# DevControl.net
KiCad netlist of a schematic drawn in EAGLE
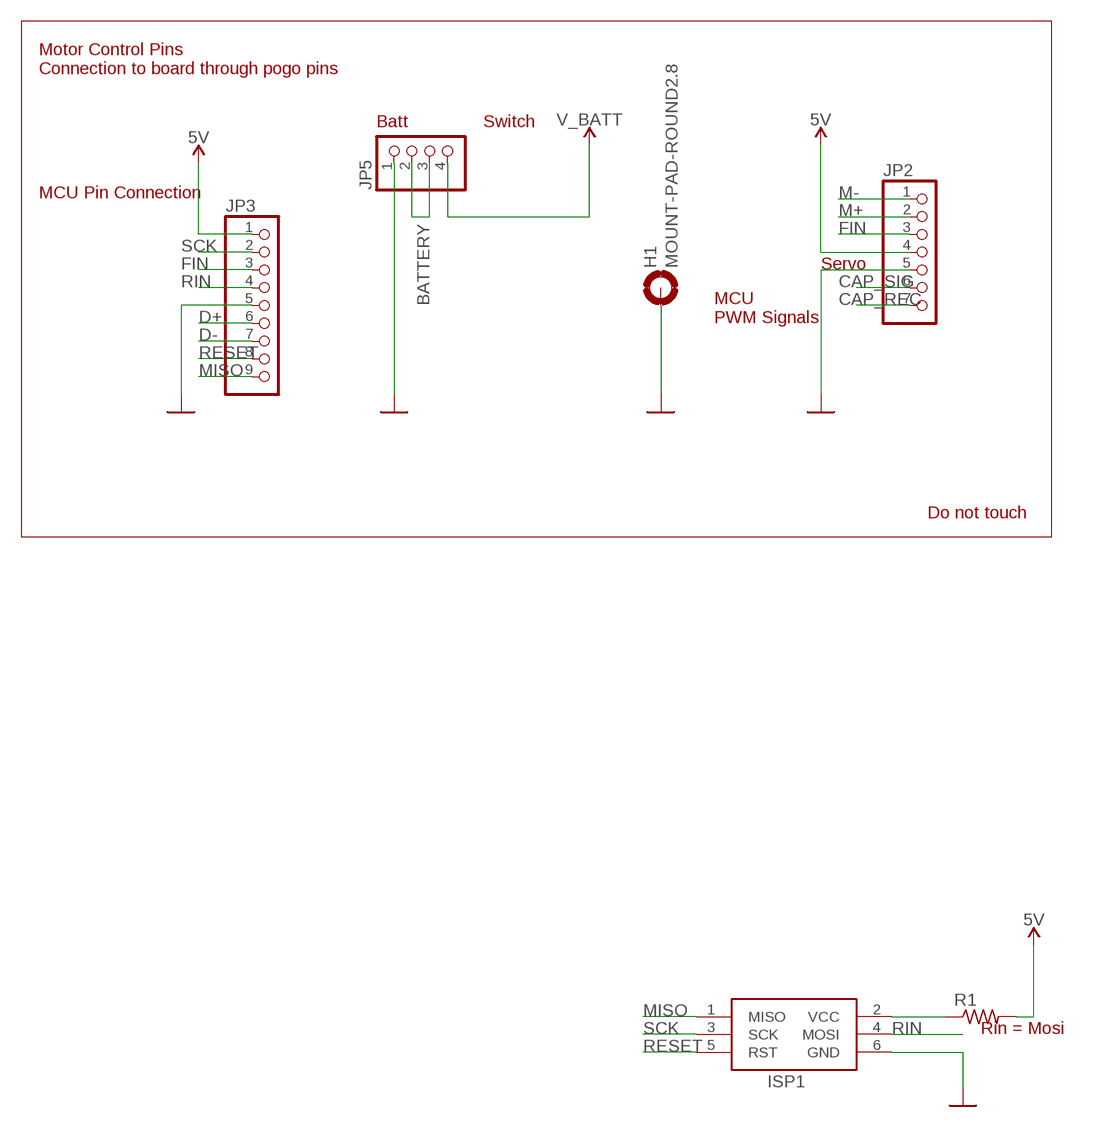
[diagram p0: schematic, sheet 1]

(export (version "E")
  (design (tool "Eeschema 10.0.6"))
  (components
    (comp (ref "H1")
      (value "MOUNT-PAD-ROUND2.8")
      (footprint "eagle-import:2,8-PAD")
      (libsource (lib "eagle-import") (part "MOUNT-PAD-ROUND2.8"))
    )
    (comp (ref "ISP1")
      (value "AVRISP-6")
      (footprint "eagle-import:AVRISP")
      (libsource (lib "eagle-import") (part "AVRISP-6"))
    )
    (comp (ref "JP2")
      (value "HEADER-1X7")
      (footprint "eagle-import:1X07_OVAL")
      (libsource (lib "eagle-import") (part "HEADER-1X7"))
    )
    (comp (ref "JP3")
      (value "HEADER-1X9")
      (footprint "eagle-import:1X09_OVAL")
      (libsource (lib "eagle-import") (part "HEADER-1X9"))
    )
    (comp (ref "JP5")
      (value "HEADER-1X4")
      (footprint "eagle-import:1X04_OVAL")
      (libsource (lib "eagle-import") (part "HEADER-1X4"))
    )
    (comp (ref "R1")
      (value "R-US_R0805")
      (footprint "eagle-import:R0805")
      (libsource (lib "eagle-import") (part "R-US_R0805"))
    )
  )
  (nets
    (net (code "1") (name "/BATTERY") (class "Default")
      (node (ref "JP5") (pin "2") (pinfunction "2_2") (pintype "passive"))
      (node (ref "JP5") (pin "3") (pinfunction "3_3") (pintype "passive"))
    )
    (net (code "2") (name "/CAP_REC") (class "Default")
      (node (ref "JP2") (pin "7") (pinfunction "7_7") (pintype "passive"))
    )
    (net (code "3") (name "/CAP_SIG") (class "Default")
      (node (ref "JP2") (pin "6") (pinfunction "6_6") (pintype "passive"))
    )
    (net (code "4") (name "/D+") (class "Default")
      (node (ref "JP3") (pin "6") (pinfunction "6_6") (pintype "passive"))
    )
    (net (code "5") (name "/D-") (class "Default")
      (node (ref "JP3") (pin "7") (pinfunction "7_7") (pintype "passive"))
    )
    (net (code "6") (name "/FIN") (class "Default")
      (node (ref "JP2") (pin "3") (pinfunction "3_3") (pintype "passive"))
      (node (ref "JP3") (pin "3") (pinfunction "3_3") (pintype "passive"))
    )
    (net (code "7") (name "/M+") (class "Default")
      (node (ref "JP2") (pin "2") (pinfunction "2_2") (pintype "passive"))
    )
    (net (code "8") (name "/M-") (class "Default")
      (node (ref "JP2") (pin "1") (pinfunction "1_1") (pintype "passive"))
    )
    (net (code "9") (name "/MISO") (class "Default")
      (node (ref "ISP1") (pin "1") (pinfunction "MISO_1") (pintype "input"))
      (node (ref "JP3") (pin "9") (pinfunction "9_9") (pintype "passive"))
    )
    (net (code "10") (name "/RESET") (class "Default")
      (node (ref "ISP1") (pin "5") (pinfunction "RST_5") (pintype "output"))
      (node (ref "JP3") (pin "8") (pinfunction "8_8") (pintype "passive"))
    )
    (net (code "11") (name "/RIN") (class "Default")
      (node (ref "ISP1") (pin "4") (pinfunction "MOSI_4") (pintype "output"))
      (node (ref "JP3") (pin "4") (pinfunction "4_4") (pintype "passive"))
    )
    (net (code "12") (name "/SCK") (class "Default")
      (node (ref "ISP1") (pin "3") (pinfunction "SCK_3") (pintype "output"))
      (node (ref "JP3") (pin "2") (pinfunction "2_2") (pintype "passive"))
    )
    (net (code "13") (name "5V") (class "Default")
      (node (ref "JP2") (pin "4") (pinfunction "4_4") (pintype "passive"))
      (node (ref "JP3") (pin "1") (pinfunction "1_1") (pintype "passive"))
      (node (ref "R1") (pin "2") (pinfunction "2_2") (pintype "passive"))
    )
    (net (code "14") (name "GND") (class "Default")
      (node (ref "H1") (pin "B2,8") (pinfunction "MOUNT_B2,8") (pintype "passive"))
      (node (ref "ISP1") (pin "6") (pinfunction "GND_6") (pintype "power_in"))
      (node (ref "JP2") (pin "5") (pinfunction "5_5") (pintype "passive"))
      (node (ref "JP3") (pin "5") (pinfunction "5_5") (pintype "passive"))
      (node (ref "JP5") (pin "1") (pinfunction "1_1") (pintype "passive"))
    )
    (net (code "15") (name "Net-(ISP1-VCC)") (class "Default")
      (node (ref "ISP1") (pin "2") (pinfunction "VCC_2") (pintype "power_in"))
      (node (ref "R1") (pin "1") (pinfunction "1_1") (pintype "passive"))
    )
    (net (code "16") (name "V_BATT") (class "Default")
      (node (ref "JP5") (pin "4") (pinfunction "4_4") (pintype "passive"))
    )
  )
)
